# DELAY.net
KiCad netlist of a schematic drawn in EAGLE
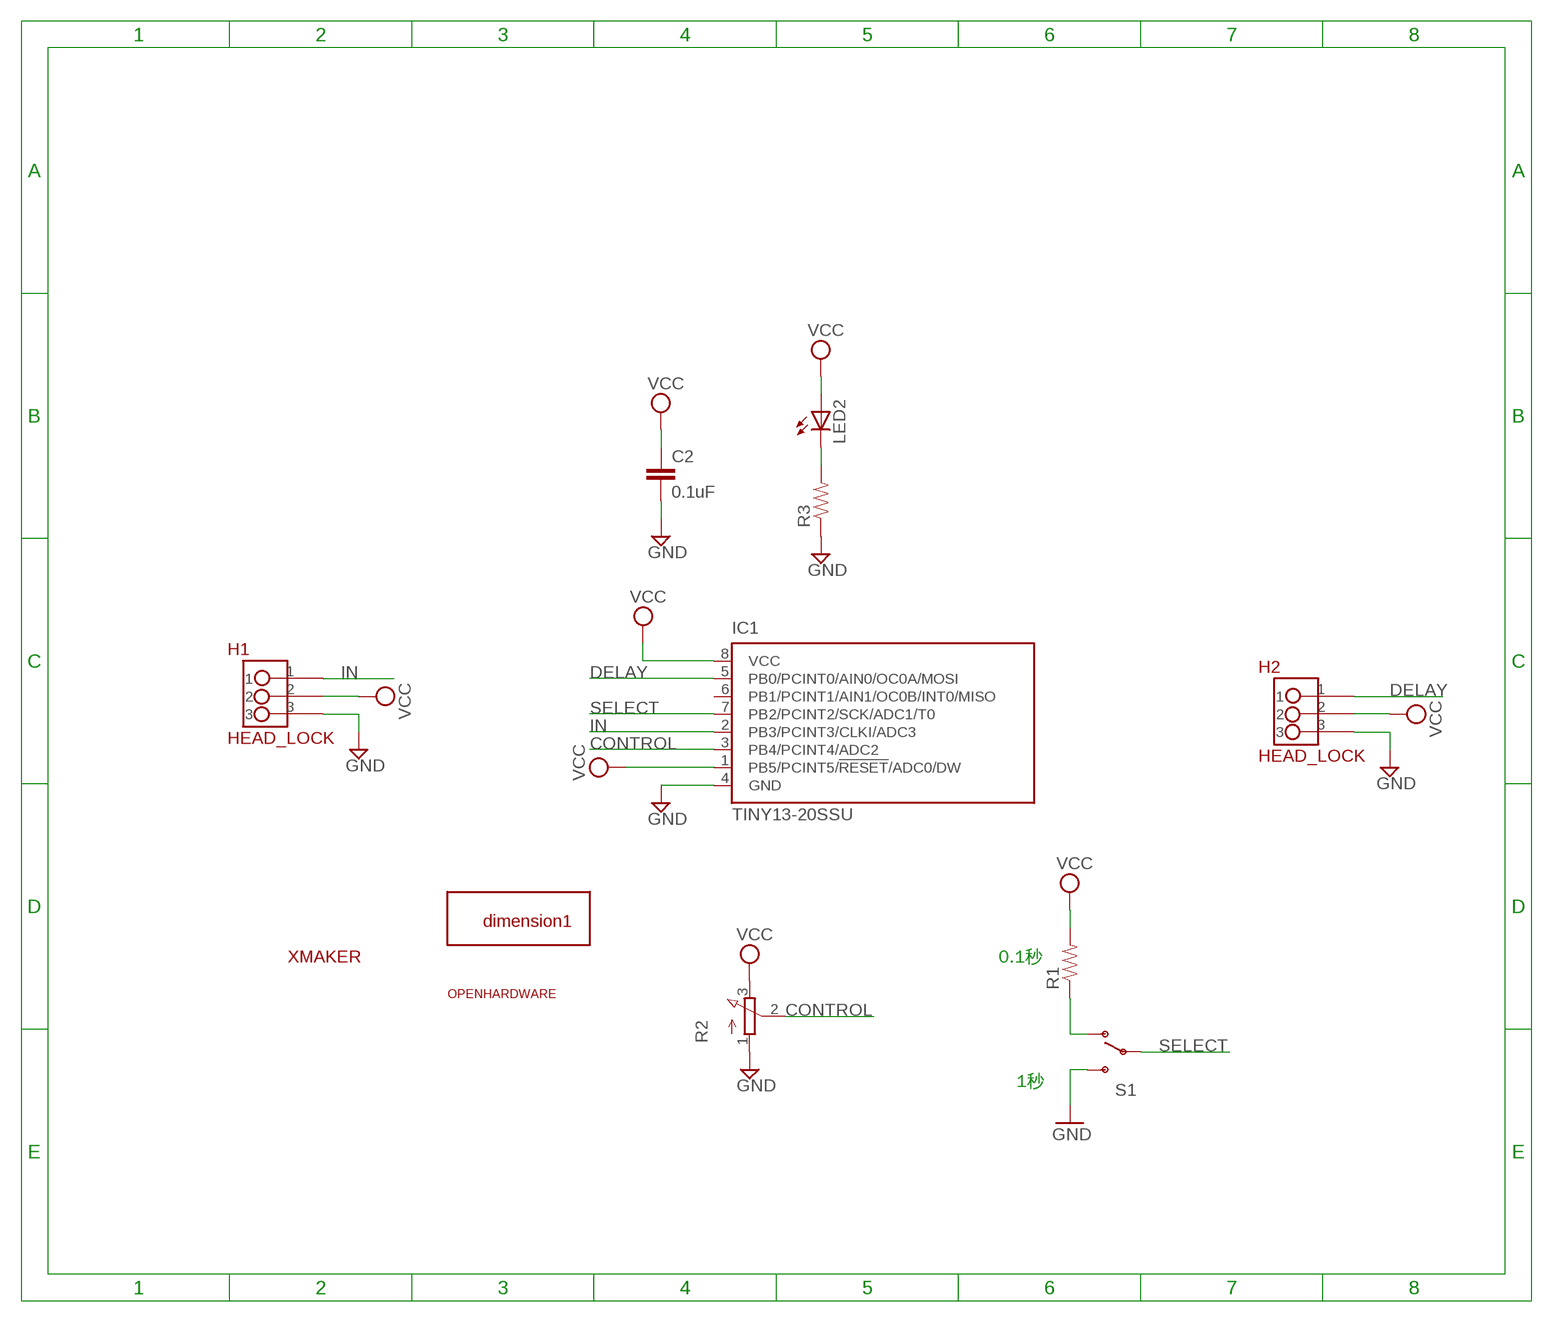
[diagram p0: schematic, sheet 1]

(export (version "E")
  (design (tool "Eeschema 10.0.6"))
  (components
    (comp (ref "C2")
      (value "0.1uF")
      (footprint "eagle-import:0603-CAP")
      (libsource (lib "eagle-import") (part "CAP0603-CAP"))
    )
    (comp (ref "H1")
      (value "HEAD_LOCK")
      (footprint "eagle-import:HEAD_LOCK")
      (libsource (lib "eagle-import") (part "HEAD_LOCK"))
    )
    (comp (ref "H2")
      (value "HEAD_LOCK")
      (footprint "eagle-import:HEAD_LOCK")
      (libsource (lib "eagle-import") (part "HEAD_LOCK"))
    )
    (comp (ref "IC1")
      (value "TINY13-20SSU")
      (footprint "eagle-import:8S1")
      (fields (field (name "MPN") "ATTINY13-20SSU"))
      (libsource (lib "eagle-import") (part "TINY13SSU-20"))
    )
    (comp (ref "LED2")
      (value "LED_ESML0603")
      (footprint "eagle-import:LED_SML0603")
      (libsource (lib "eagle-import") (part "LED_ESML0603"))
    )
    (comp (ref "R1")
      (value "RESISTOR0603-RES")
      (footprint "eagle-import:0603-RES")
      (libsource (lib "eagle-import") (part "RESISTOR0603-RES"))
    )
    (comp (ref "R2")
      (value "3RP/1610N")
      (footprint "eagle-import:3RP_1610N")
      (libsource (lib "eagle-import") (part "3RP/1610N"))
    )
    (comp (ref "R3")
      (value "0.27OHM-1/10W-1%(0603)")
      (footprint "eagle-import:0603-RES")
      (libsource (lib "eagle-import") (part "0.27OHM-1/10W-1%(0603)"))
    )
    (comp (ref "S1")
      (value "SWITCH-SPDTKIT")
      (footprint "eagle-import:SWITCH-SPDT_KIT")
      (libsource (lib "eagle-import") (part "SWITCH-SPDTKIT"))
    )
    (comp (ref "U$1")
      (value "XMAKERLOGO2")
      (footprint "eagle-import:XMAKERLOGO2")
      (libsource (lib "eagle-import") (part "XMAKERLOGO2"))
    )
    (comp (ref "U$2")
      (value "DIMENSION1")
      (footprint "eagle-import:DIMENSION1")
      (libsource (lib "eagle-import") (part "DIMENSION1"))
    )
    (comp (ref "U$3")
      (value "OPENHARDWARE")
      (footprint "eagle-import:OPENHARDWARE")
      (libsource (lib "eagle-import") (part "OPENHARDWARE"))
    )
  )
  (nets
    (net (code "1") (name "/CONTROL") (class "Default")
      (node (ref "IC1") (pin "3") (pinfunction "PB4/PCINT4/ADC2_3") (pintype "bidirectional"))
      (node (ref "R2") (pin "2") (pinfunction "S_2") (pintype "passive"))
    )
    (net (code "2") (name "/DELAY") (class "Default")
      (node (ref "H2") (pin "1") (pinfunction "1_1") (pintype "passive"))
      (node (ref "IC1") (pin "5") (pinfunction "PB0/PCINT0/AIN0/OC0A/MOSI_5") (pintype "bidirectional"))
    )
    (net (code "3") (name "/IN") (class "Default")
      (node (ref "H1") (pin "1") (pinfunction "1_1") (pintype "passive"))
      (node (ref "IC1") (pin "2") (pinfunction "PB3/PCINT3/CLKI/ADC3_2") (pintype "bidirectional"))
    )
    (net (code "4") (name "/SELECT") (class "Default")
      (node (ref "IC1") (pin "7") (pinfunction "PB2/PCINT2/SCK/ADC1/T0_7") (pintype "bidirectional"))
      (node (ref "S1") (pin "2") (pinfunction "P_2") (pintype "passive"))
    )
    (net (code "5") (name "GND") (class "Default")
      (node (ref "C2") (pin "2") (pinfunction "2_2") (pintype "passive"))
      (node (ref "H1") (pin "3") (pinfunction "3_3") (pintype "passive"))
      (node (ref "H2") (pin "3") (pinfunction "3_3") (pintype "passive"))
      (node (ref "IC1") (pin "4") (pinfunction "GND_4") (pintype "power_in"))
      (node (ref "R2") (pin "1") (pinfunction "A_1") (pintype "passive"))
      (node (ref "R3") (pin "1") (pinfunction "1_1") (pintype "passive"))
      (node (ref "S1") (pin "3") (pinfunction "S_3") (pintype "passive"))
    )
    (net (code "6") (name "Net-(LED2-PadC)") (class "Default")
      (node (ref "LED2") (pin "C") (pinfunction "C_C") (pintype "passive"))
      (node (ref "R3") (pin "2") (pinfunction "2_2") (pintype "passive"))
    )
    (net (code "7") (name "Net-(S1-O)") (class "Default")
      (node (ref "R1") (pin "1") (pinfunction "1_1") (pintype "passive"))
      (node (ref "S1") (pin "1") (pinfunction "O_1") (pintype "passive"))
    )
    (net (code "8") (name "VCC") (class "Default")
      (node (ref "C2") (pin "1") (pinfunction "1_1") (pintype "passive"))
      (node (ref "H1") (pin "2") (pinfunction "2_2") (pintype "passive"))
      (node (ref "H2") (pin "2") (pinfunction "2_2") (pintype "passive"))
      (node (ref "IC1") (pin "1") (pinfunction "PB5/PCINT5/~{RESET}/ADC0/DW_1") (pintype "bidirectional"))
      (node (ref "IC1") (pin "8") (pinfunction "VCC_8") (pintype "power_in"))
      (node (ref "LED2") (pin "A") (pinfunction "A_A") (pintype "passive"))
      (node (ref "R1") (pin "2") (pinfunction "2_2") (pintype "passive"))
      (node (ref "R2") (pin "3") (pinfunction "E_3") (pintype "passive"))
    )
    (net (code "9") (name "unconnected-(IC1-PB1{slash}PCINT1{slash}AIN1{slash}OC0B{slash}INT0{slash}MISO-Pad6)") (class "Default")
      (node (ref "IC1") (pin "6") (pinfunction "PB1/PCINT1/AIN1/OC0B/INT0/MISO_6") (pintype "bidirectional"))
    )
  )
)
